# CH340.net
KiCad netlist of a schematic drawn in Altium Designer
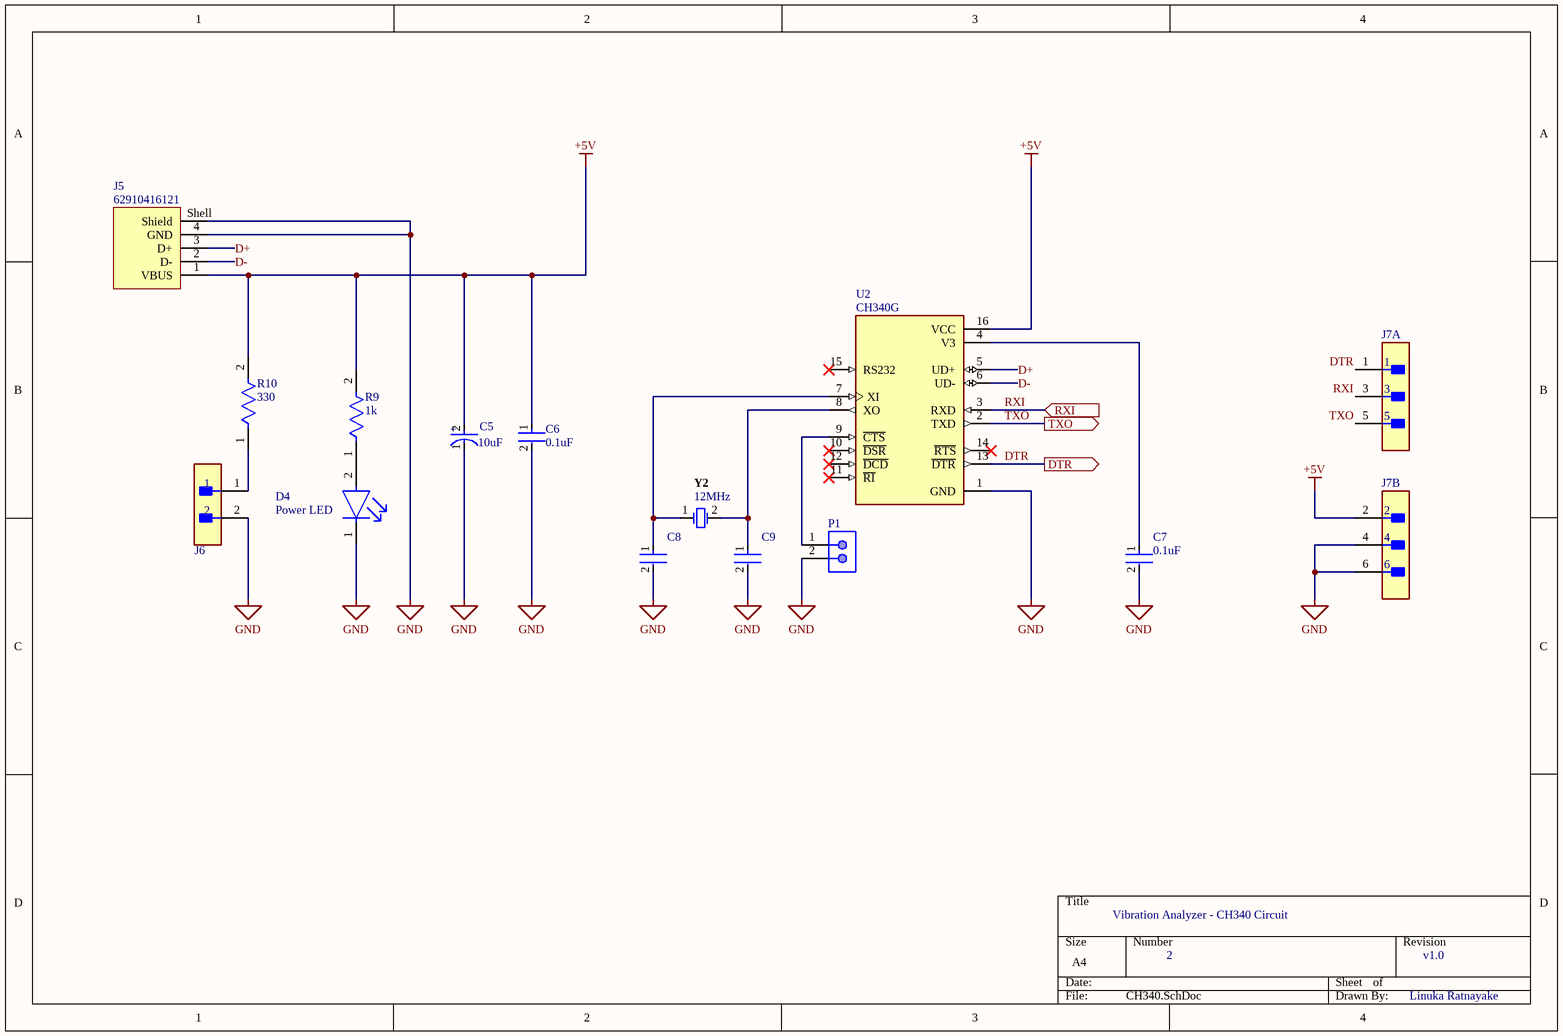
[diagram p0: CH340.SchDoc]

(export (version "E")
  (design (tool "Eeschema 10.0.6"))
  (components
    (comp (ref "C5")
      (value "EEE1VA100SR")
      (footprint "FP-SC-MFG")
      (description "CAP ALUM 10UF 20% 35V SMD")
      (fields
        (field (name "CAPACITANCE") "10uF")
        (field (name "TOLERANCE") "20%")
        (field (name "VOLTAGE") "35V")
      )
      (libsource (lib "Altium Content Vault") (part "203bc49f2ac43e59fd269a8c329ed05"))
    )
    (comp (ref "C6")
      (value "GRM31M1X1H104JA01L")
      (footprint "FP-GRM31M-0_15-IPC_A")
      (fields
        (field (name "VOLTAGE") "50V")
        (field (name "TOLERANCE") "5%")
        (field (name "CAPACITANCE") "0.1uF")
      )
      (libsource (lib "Altium Content Vault") (part "b4654b650e69147ec39a6b967a45e02"))
    )
    (comp (ref "C7")
      (value "GRM31M1X1H104JA01L")
      (footprint "FP-GRM31M-0_15-IPC_A")
      (fields
        (field (name "VOLTAGE") "50V")
        (field (name "TOLERANCE") "5%")
        (field (name "CAPACITANCE") "0.1uF")
      )
      (libsource (lib "Altium Content Vault") (part "b4654b650e69147ec39a6b967a45e02"))
    )
    (comp (ref "C8")
      (value "GRM31M1X1H104JA01L")
      (footprint "FP-GRM31M-0_15-IPC_A")
      (fields (field (name "VOLTAGE") "50V") (field (name "TOLERANCE") "5%"))
      (libsource (lib "Altium Content Vault") (part "b4654b650e69147ec39a6b967a45e02"))
    )
    (comp (ref "C9")
      (value "GRM31M1X1H104JA01L")
      (footprint "FP-GRM31M-0_15-IPC_A")
      (fields (field (name "VOLTAGE") "50V") (field (name "TOLERANCE") "5%"))
      (libsource (lib "Altium Content Vault") (part "b4654b650e69147ec39a6b967a45e02"))
    )
    (comp (ref "D4")
      (value "HSMG-C150")
      (footprint "FP-HSMG-C150-MFG")
      (description "LED GREEN DIFFUSED 1206 SMD")
      (fields
        (field (name "MANUFACTURER") "Broadcom")
        (field (name "OCTOPART") "https://octopart.com/hsmg-c150-broadcom-71131304")
        (field (name "COLOR") "Power LED")
      )
      (libsource (lib "Altium Content Vault") (part "8706943c75ba83719d021d2fdc84c58"))
    )
    (comp (ref "J5")
      (value "62910416121")
      (footprint "62910416121")
      (libsource (lib "Altium Content Vault") (part "USB 2.0_Type B_Receptacle_1 Port"))
    )
    (comp (ref "J6")
      (value "B2B-XH-A(LF)(SN)")
      (footprint "FP-B2B-XH-A_LF_SN-MFG")
      (description "CONN HEADER VERT 2POS 2.5MM")
      (libsource (lib "Altium Content Vault") (part "3bc925449376181038e59eaffc5286c"))
    )
    (comp (ref "J7")
      (value "M20-9980346")
      (footprint "FP-M20-9980346-MFG")
      (description "CONN HEADER VERT 6POS 2.54MM")
      (fields
        (field (name "MANUFACTURER") "Harwin")
        (field (name "OCTOPART") "https://octopart.com/m20-9980346-harwin-5436545")
      )
      (libsource (lib "Altium Content Vault") (part "2654a11fb13586ecb194516b1c997bc"))
    )
    (comp (ref "P1")
      (value "22-27-2021")
      (footprint "MOLX-22-27-2021_V")
      (fields (field (name "MANUFACTURER") "Molex") (field (name "PARTNUMBER") "0022272021"))
      (libsource (lib "Altium Content Vault") (part "CN-1P-M-R2"))
    )
    (comp (ref "R9")
      (value "MCR18EZPF30R0")
      (footprint "FP-MCR18-IPC_B")
      (description "Thick Film Chip Resistor, 1206, 30Ω, 1%, 100ppm/°C, 0.25W, 200V")
      (fields (field (name "RESISTANCE") "1k") (field (name "TOLERANCE") "1%"))
      (libsource (lib "Altium Content Vault") (part "1029c3af85768c4190bb7ad29bc67b5"))
    )
    (comp (ref "R10")
      (value "MCR18EZPF30R0")
      (footprint "FP-MCR18-IPC_B")
      (description "Thick Film Chip Resistor, 1206, 30Ω, 1%, 100ppm/°C, 0.25W, 200V")
      (fields (field (name "RESISTANCE") "330") (field (name "TOLERANCE") "1%"))
      (libsource (lib "Altium Content Vault") (part "1029c3af85768c4190bb7ad29bc67b5"))
    )
    (comp (ref "U2")
      (value "CH340G")
      (footprint "SOIC127P600X180-16N")
      (description "USB Interface Integrated Circuit")
      (fields (field (name "MP") "Ch340G") (field (name "MF") "WCH"))
      (libsource (lib "CH340G") (part "CH340G"))
    )
    (comp (ref "Y2")
      (value "12MHz")
      (footprint "FOX-FOXSLF-2_V")
      (description "Resistance Weld Thru-Hole Crystal, 12 MHz, +/-30 ppm, -20 to 70 degC, 2-Pin THD, RoHS, Bulk")
      (fields (field (name "Comment") "FOXSLF/120-20"))
      (libsource (lib "Altium Content Vault") (part "XTAL-1-2-2"))
    )
  )
  (nets
    (net (code "1") (name "+5V") (class "Default")
      (node (ref "C5") (pin "2") (pinfunction "A_2") (pintype "passive"))
      (node (ref "C6") (pin "1") (pinfunction "1_1") (pintype "passive"))
      (node (ref "J5") (pin "1") (pinfunction "VBUS_1") (pintype "passive"))
      (node (ref "J7") (pin "2") (pinfunction "2_2") (pintype "passive"))
      (node (ref "R10") (pin "2") (pinfunction "2_2") (pintype "passive"))
      (node (ref "R9") (pin "2") (pinfunction "2_2") (pintype "passive"))
      (node (ref "U2") (pin "16") (pinfunction "VCC_16") (pintype "power_in"))
    )
    (net (code "2") (name "/D+") (class "Default")
      (node (ref "J5") (pin "3") (pinfunction "D+_3") (pintype "passive"))
      (node (ref "U2") (pin "5") (pinfunction "UD+_5") (pintype "bidirectional"))
    )
    (net (code "3") (name "/D-") (class "Default")
      (node (ref "J5") (pin "2") (pinfunction "D-_2") (pintype "passive"))
      (node (ref "U2") (pin "6") (pinfunction "UD-_6") (pintype "bidirectional"))
    )
    (net (code "4") (name "/DTR") (class "Default")
      (node (ref "J7") (pin "1") (pinfunction "1_1") (pintype "passive"))
      (node (ref "U2") (pin "13") (pinfunction "~{DTR}_13") (pintype "output"))
    )
    (net (code "5") (name "/RXI") (class "Default")
      (node (ref "J7") (pin "3") (pinfunction "3_3") (pintype "passive"))
      (node (ref "U2") (pin "3") (pinfunction "RXD_3") (pintype "input"))
    )
    (net (code "6") (name "/TXO") (class "Default")
      (node (ref "J7") (pin "5") (pinfunction "5_5") (pintype "passive"))
      (node (ref "U2") (pin "2") (pinfunction "TXD_2") (pintype "output"))
    )
    (net (code "7") (name "GND") (class "Default")
      (node (ref "C5") (pin "1") (pinfunction "C_1") (pintype "passive"))
      (node (ref "C6") (pin "2") (pinfunction "2_2") (pintype "passive"))
      (node (ref "C7") (pin "2") (pinfunction "2_2") (pintype "passive"))
      (node (ref "C8") (pin "2") (pinfunction "2_2") (pintype "passive"))
      (node (ref "C9") (pin "2") (pinfunction "2_2") (pintype "passive"))
      (node (ref "D4") (pin "1") (pinfunction "C_1") (pintype "passive"))
      (node (ref "J5") (pin "4") (pinfunction "GND_4") (pintype "passive"))
      (node (ref "J5") (pin "Shell") (pinfunction "Shield_Shell") (pintype "passive"))
      (node (ref "J6") (pin "2") (pinfunction "2_2") (pintype "passive"))
      (node (ref "J7") (pin "4") (pinfunction "4_4") (pintype "passive"))
      (node (ref "J7") (pin "6") (pinfunction "6_6") (pintype "passive"))
      (node (ref "P1") (pin "2") (pinfunction "2_2") (pintype "passive"))
      (node (ref "U2") (pin "1") (pinfunction "GND_1") (pintype "power_in"))
    )
    (net (code "8") (name "Net-(D4-A)") (class "Default")
      (node (ref "D4") (pin "2") (pinfunction "A_2") (pintype "passive"))
      (node (ref "R9") (pin "1") (pinfunction "1_1") (pintype "passive"))
    )
    (net (code "9") (name "Net-(J6-Pad1)") (class "Default")
      (node (ref "J6") (pin "1") (pinfunction "1_1") (pintype "passive"))
      (node (ref "R10") (pin "1") (pinfunction "1_1") (pintype "passive"))
    )
    (net (code "10") (name "Net-(U2-V3)") (class "Default")
      (node (ref "C7") (pin "1") (pinfunction "1_1") (pintype "passive"))
      (node (ref "U2") (pin "4") (pinfunction "V3_4") (pintype "power_in"))
    )
    (net (code "11") (name "Net-(U2-XI)") (class "Default")
      (node (ref "C8") (pin "1") (pinfunction "1_1") (pintype "passive"))
      (node (ref "U2") (pin "7") (pinfunction "XI_7") (pintype "input"))
      (node (ref "Y2") (pin "1") (pinfunction "1_1") (pintype "passive"))
    )
    (net (code "12") (name "Net-(U2-XO)") (class "Default")
      (node (ref "C9") (pin "1") (pinfunction "1_1") (pintype "passive"))
      (node (ref "U2") (pin "8") (pinfunction "XO_8") (pintype "output"))
      (node (ref "Y2") (pin "2") (pinfunction "2_2") (pintype "passive"))
    )
    (net (code "13") (name "Net-(U2-~{CTS})") (class "Default")
      (node (ref "P1") (pin "1") (pinfunction "1_1") (pintype "passive"))
      (node (ref "U2") (pin "9") (pinfunction "~{CTS}_9") (pintype "input"))
    )
    (net (code "14") (name "unconnected-(U2-RS232-Pad15)") (class "Default")
      (node (ref "U2") (pin "15") (pinfunction "RS232_15") (pintype "input+no_connect"))
    )
    (net (code "15") (name "unconnected-(U2-~{DCD}-Pad12)") (class "Default")
      (node (ref "U2") (pin "12") (pinfunction "~{DCD}_12") (pintype "input+no_connect"))
    )
    (net (code "16") (name "unconnected-(U2-~{DSR}-Pad10)") (class "Default")
      (node (ref "U2") (pin "10") (pinfunction "~{DSR}_10") (pintype "input+no_connect"))
    )
    (net (code "17") (name "unconnected-(U2-~{RI}-Pad11)") (class "Default")
      (node (ref "U2") (pin "11") (pinfunction "~{RI}_11") (pintype "input+no_connect"))
    )
    (net (code "18") (name "unconnected-(U2-~{RTS}-Pad14)") (class "Default")
      (node (ref "U2") (pin "14") (pinfunction "~{RTS}_14") (pintype "output+no_connect"))
    )
  )
)
